# POWER.net
KiCad netlist of a schematic drawn in Altium Designer
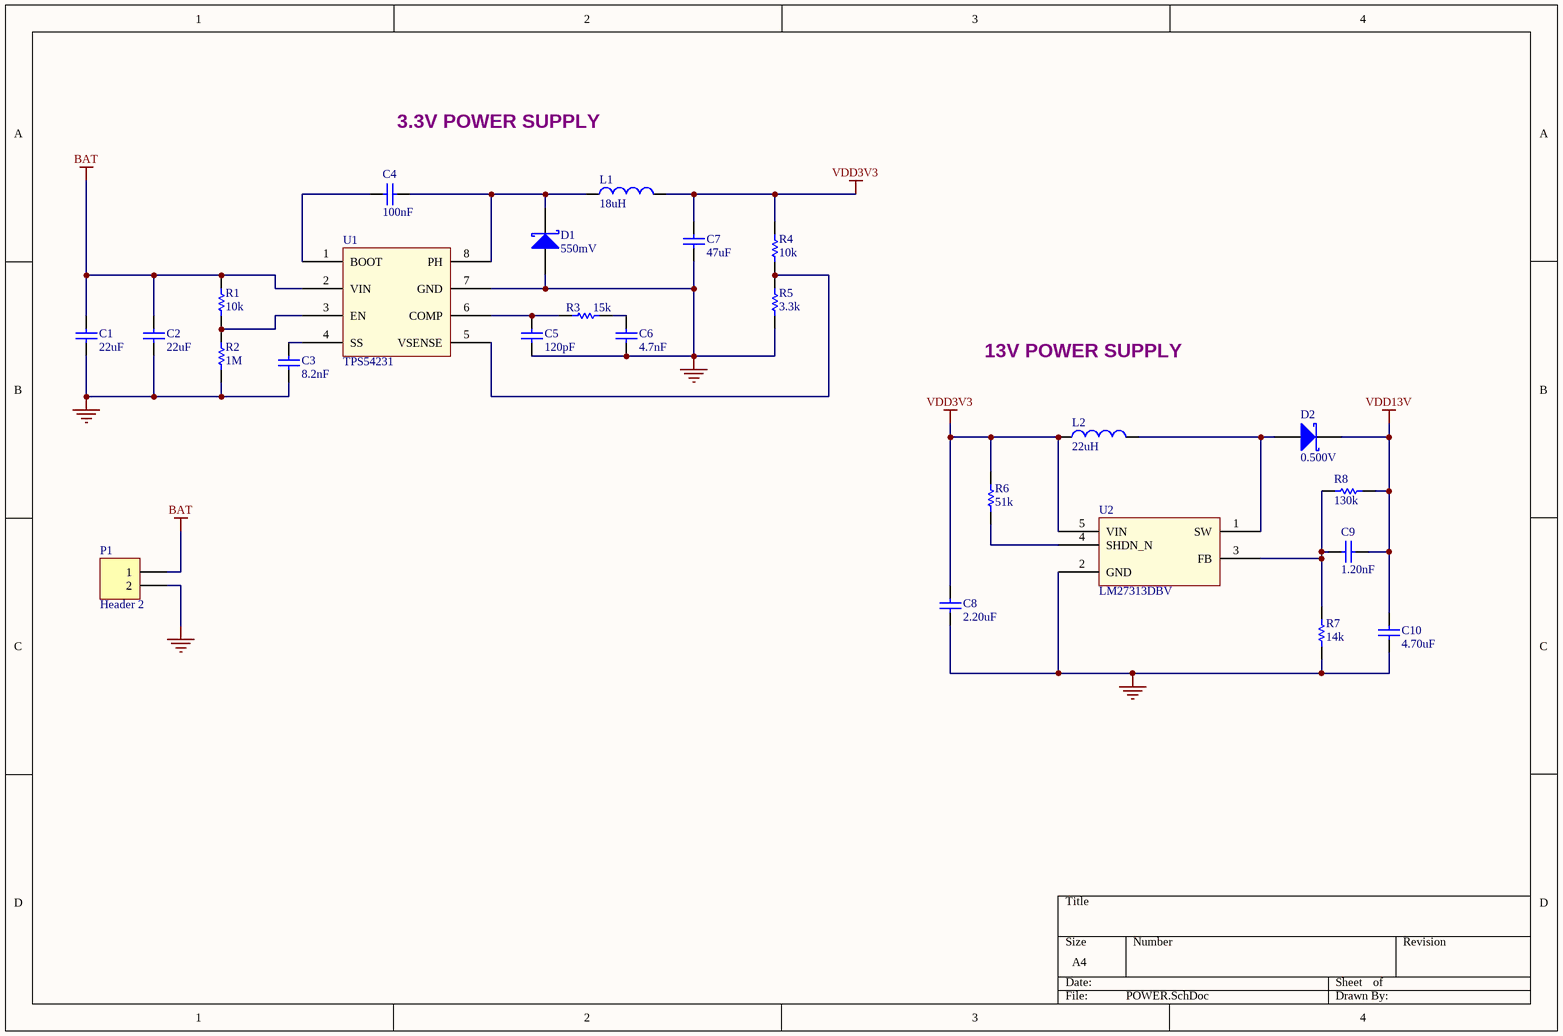
[diagram p0: POWER.SchDoc]

(export (version "E")
  (design (tool "Eeschema 10.0.6"))
  (components
    (comp (ref "C1")
      (value "22uF")
      (footprint "CAPC1608X90N")
      (description "50V")
      (libsource (lib "POP_lib") (part "Capacitor"))
    )
    (comp (ref "C2")
      (value "22uF")
      (footprint "CAPC1608X90N")
      (description "50V")
      (libsource (lib "POP_lib") (part "Capacitor"))
    )
    (comp (ref "C3")
      (value "8.2nF")
      (footprint "CAPC1608X90N")
      (description "25V")
      (libsource (lib "POP_lib") (part "Capacitor"))
    )
    (comp (ref "C4")
      (value "100nF")
      (footprint "CAPC1608X90N")
      (description "10V")
      (libsource (lib "POP_lib") (part "Capacitor"))
    )
    (comp (ref "C5")
      (value "120pF")
      (footprint "CAPC1608X90N")
      (description "50V")
      (libsource (lib "POP_lib") (part "Capacitor"))
    )
    (comp (ref "C6")
      (value "4.7nF")
      (footprint "CAPC1608X90N")
      (description "25V")
      (libsource (lib "POP_lib") (part "Capacitor"))
    )
    (comp (ref "C7")
      (value "47uF")
      (footprint "CAPMP7343X310N")
      (description "GRM32ER60J476ME20L 3225 !")
      (libsource (lib "POP_lib") (part "Capacitor"))
    )
    (comp (ref "C8")
      (value "2.20uF")
      (footprint "CAPC1608X90N")
      (description "6.3V")
      (libsource (lib "POP_lib") (part "Capacitor"))
    )
    (comp (ref "C9")
      (value "1.20nF")
      (footprint "CAPC1608X90N")
      (description "50V")
      (libsource (lib "POP_lib") (part "Capacitor"))
    )
    (comp (ref "C10")
      (value "4.70uF")
      (footprint "CAPC1608X90N")
      (libsource (lib "POP_lib") (part "Capacitor"))
    )
    (comp (ref "D1")
      (value "550mV")
      (footprint "SOD123")
      (description "Diode")
      (libsource (lib "POP_lib") (part "D_ZENER"))
    )
    (comp (ref "D2")
      (value "0.500V")
      (footprint "SOD123")
      (description "Diode")
      (libsource (lib "POP_lib") (part "D_ZENER"))
    )
    (comp (ref "L1")
      (value "18uH")
      (footprint "SD43 Inductor")
      (description "Inductor")
      (libsource (lib "POP_lib") (part "Inductor"))
    )
    (comp (ref "L2")
      (value "22uH")
      (footprint "ME3220 Inductor")
      (description "Inductor")
      (libsource (lib "POP_lib") (part "Inductor"))
    )
    (comp (ref "P1")
      (value "Header 2")
      (footprint "2477")
      (description "Header, 2-Pin")
      (libsource (lib "POP_lib") (part "Header 2"))
    )
    (comp (ref "R1")
      (value "10k")
      (footprint "RESC1608X55N")
      (description "Resistor")
      (libsource (lib "POP_lib") (part "Resistor"))
    )
    (comp (ref "R2")
      (value "1M")
      (footprint "RESC1608X55N")
      (description "Resistor")
      (libsource (lib "POP_lib") (part "Resistor"))
    )
    (comp (ref "R3")
      (value "15k")
      (footprint "RESC1608X55N")
      (description "Resistor")
      (libsource (lib "POP_lib") (part "Resistor"))
    )
    (comp (ref "R4")
      (value "10k")
      (footprint "RESC1608X55N")
      (description "Resistor")
      (libsource (lib "POP_lib") (part "Resistor"))
    )
    (comp (ref "R5")
      (value "3.3k")
      (footprint "RESC1608X55N")
      (description "Resistor")
      (libsource (lib "POP_lib") (part "Resistor"))
    )
    (comp (ref "R6")
      (value "51k")
      (footprint "RESC1608X55N")
      (description "Resistor")
      (libsource (lib "POP_lib") (part "Resistor"))
    )
    (comp (ref "R7")
      (value "14k")
      (footprint "RESC1608X55N")
      (description "Resistor")
      (libsource (lib "POP_lib") (part "Resistor"))
    )
    (comp (ref "R8")
      (value "130k")
      (footprint "RESC1608X55N")
      (description "Resistor")
      (libsource (lib "POP_lib") (part "Resistor"))
    )
    (comp (ref "U1") (value "TPS54231") (footprint "SOIC-8") (libsource (lib "POP_lib") (part "TPS54231")))
    (comp (ref "U2")
      (value "LM27313DBV")
      (footprint "SOT23-5")
      (libsource (lib "POP_lib") (part "LM27313DBV"))
    )
  )
  (nets
    (net (code "1") (name "BAT") (class "Default")
      (node (ref "C1") (pin "2") (pinfunction "2_2") (pintype "passive"))
      (node (ref "C2") (pin "2") (pinfunction "2_2") (pintype "passive"))
      (node (ref "P1") (pin "1") (pinfunction "1_1") (pintype "passive"))
      (node (ref "R1") (pin "1") (pinfunction "1_1") (pintype "passive"))
      (node (ref "U1") (pin "2") (pinfunction "VIN_2") (pintype "passive"))
    )
    (net (code "2") (name "GND") (class "Default")
      (node (ref "C1") (pin "1") (pinfunction "1_1") (pintype "passive"))
      (node (ref "C10") (pin "1") (pinfunction "1_1") (pintype "passive"))
      (node (ref "C2") (pin "1") (pinfunction "1_1") (pintype "passive"))
      (node (ref "C3") (pin "1") (pinfunction "1_1") (pintype "passive"))
      (node (ref "C5") (pin "1") (pinfunction "1_1") (pintype "passive"))
      (node (ref "C6") (pin "1") (pinfunction "1_1") (pintype "passive"))
      (node (ref "C7") (pin "1") (pinfunction "1_1") (pintype "passive"))
      (node (ref "C8") (pin "1") (pinfunction "1_1") (pintype "passive"))
      (node (ref "D1") (pin "1") (pinfunction "A_1") (pintype "passive"))
      (node (ref "P1") (pin "2") (pinfunction "2_2") (pintype "passive"))
      (node (ref "R2") (pin "2") (pinfunction "2_2") (pintype "passive"))
      (node (ref "R5") (pin "1") (pinfunction "1_1") (pintype "passive"))
      (node (ref "R7") (pin "1") (pinfunction "1_1") (pintype "passive"))
      (node (ref "U1") (pin "7") (pinfunction "GND_7") (pintype "passive"))
      (node (ref "U2") (pin "2") (pinfunction "GND_2") (pintype "passive"))
    )
    (net (code "3") (name "Net-(C6-Pad2)") (class "Default")
      (node (ref "C6") (pin "2") (pinfunction "2_2") (pintype "passive"))
      (node (ref "R3") (pin "1") (pinfunction "1_1") (pintype "passive"))
    )
    (net (code "4") (name "Net-(D1-K)") (class "Default")
      (node (ref "C4") (pin "1") (pinfunction "1_1") (pintype "passive"))
      (node (ref "D1") (pin "2") (pinfunction "K_2") (pintype "passive"))
      (node (ref "L1") (pin "1") (pinfunction "1_1") (pintype "passive"))
      (node (ref "U1") (pin "8") (pinfunction "PH_8") (pintype "passive"))
    )
    (net (code "5") (name "Net-(D2-A)") (class "Default")
      (node (ref "D2") (pin "1") (pinfunction "A_1") (pintype "passive"))
      (node (ref "L2") (pin "2") (pinfunction "2_2") (pintype "passive"))
      (node (ref "U2") (pin "1") (pinfunction "SW_1") (pintype "passive"))
    )
    (net (code "6") (name "Net-(U1-BOOT)") (class "Default")
      (node (ref "C4") (pin "2") (pinfunction "2_2") (pintype "passive"))
      (node (ref "U1") (pin "1") (pinfunction "BOOT_1") (pintype "passive"))
    )
    (net (code "7") (name "Net-(U1-COMP)") (class "Default")
      (node (ref "C5") (pin "2") (pinfunction "2_2") (pintype "passive"))
      (node (ref "R3") (pin "2") (pinfunction "2_2") (pintype "passive"))
      (node (ref "U1") (pin "6") (pinfunction "COMP_6") (pintype "passive"))
    )
    (net (code "8") (name "Net-(U1-EN)") (class "Default")
      (node (ref "R1") (pin "2") (pinfunction "2_2") (pintype "passive"))
      (node (ref "R2") (pin "1") (pinfunction "1_1") (pintype "passive"))
      (node (ref "U1") (pin "3") (pinfunction "EN_3") (pintype "passive"))
    )
    (net (code "9") (name "Net-(U1-SS)") (class "Default")
      (node (ref "C3") (pin "2") (pinfunction "2_2") (pintype "passive"))
      (node (ref "U1") (pin "4") (pinfunction "SS_4") (pintype "passive"))
    )
    (net (code "10") (name "Net-(U1-VSENSE)") (class "Default")
      (node (ref "R4") (pin "1") (pinfunction "1_1") (pintype "passive"))
      (node (ref "R5") (pin "2") (pinfunction "2_2") (pintype "passive"))
      (node (ref "U1") (pin "5") (pinfunction "VSENSE_5") (pintype "passive"))
    )
    (net (code "11") (name "Net-(U2-FB)") (class "Default")
      (node (ref "C9") (pin "1") (pinfunction "1_1") (pintype "passive"))
      (node (ref "R7") (pin "2") (pinfunction "2_2") (pintype "passive"))
      (node (ref "R8") (pin "1") (pinfunction "1_1") (pintype "passive"))
      (node (ref "U2") (pin "3") (pinfunction "FB_3") (pintype "passive"))
    )
    (net (code "12") (name "Net-(U2-SHDN_N)") (class "Default")
      (node (ref "R6") (pin "1") (pinfunction "1_1") (pintype "passive"))
      (node (ref "U2") (pin "4") (pinfunction "SHDN_N_4") (pintype "passive"))
    )
    (net (code "13") (name "VDD3V3") (class "Default")
      (node (ref "C7") (pin "2") (pinfunction "2_2") (pintype "passive"))
      (node (ref "C8") (pin "2") (pinfunction "2_2") (pintype "passive"))
      (node (ref "L1") (pin "2") (pinfunction "2_2") (pintype "passive"))
      (node (ref "L2") (pin "1") (pinfunction "1_1") (pintype "passive"))
      (node (ref "R4") (pin "2") (pinfunction "2_2") (pintype "passive"))
      (node (ref "R6") (pin "2") (pinfunction "2_2") (pintype "passive"))
      (node (ref "U2") (pin "5") (pinfunction "VIN_5") (pintype "passive"))
    )
    (net (code "14") (name "VDD13V") (class "Default")
      (node (ref "C10") (pin "2") (pinfunction "2_2") (pintype "passive"))
      (node (ref "C9") (pin "2") (pinfunction "2_2") (pintype "passive"))
      (node (ref "D2") (pin "2") (pinfunction "K_2") (pintype "passive"))
      (node (ref "R8") (pin "2") (pinfunction "2_2") (pintype "passive"))
    )
  )
)
